# drv8313.net
KiCad netlist of a schematic drawn in Altium Designer
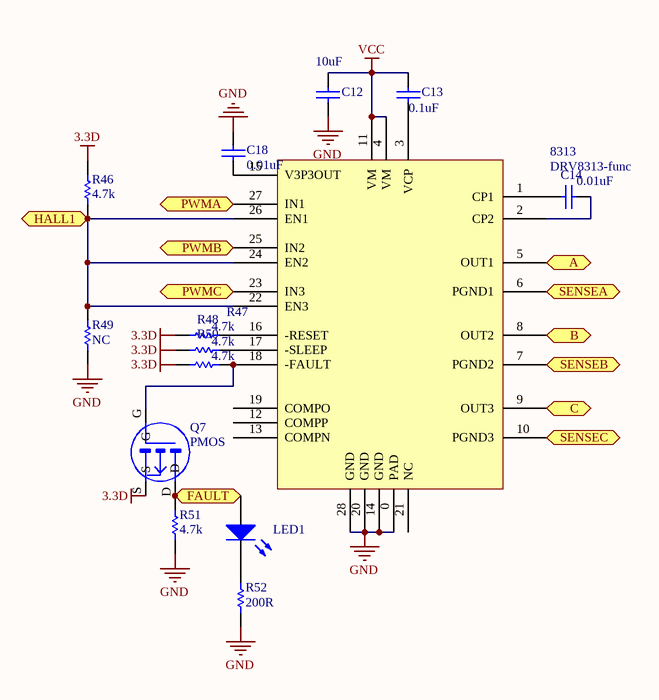
[diagram p0: drv8313.SchDoc]

(export (version "E")
  (design (tool "Eeschema 10.0.6"))
  (components
    (comp (ref "8313")
      (value "DRV8313-func")
      (footprint "DRV8313")
      (libsource (lib "sch") (part "DRV8313-func"))
    )
    (comp (ref "C12")
      (value "10uF")
      (footprint "0805")
      (description "Capacitor")
      (fields (field (name "PUBLISHER") "Altium Limited"))
      (libsource (lib "PCB_Project") (part "Cap"))
    )
    (comp (ref "C13")
      (value "0.1uF")
      (footprint "0603")
      (description "Capacitor")
      (fields (field (name "PUBLISHER") "Altium Limited"))
      (libsource (lib "PCB_Project") (part "Cap"))
    )
    (comp (ref "C14")
      (value "0.01uF")
      (footprint "0603")
      (description "Capacitor")
      (fields (field (name "PUBLISHER") "Altium Limited"))
      (libsource (lib "PCB_Project") (part "Cap"))
    )
    (comp (ref "C18")
      (value "0.01uF")
      (footprint "0603")
      (description "Capacitor")
      (fields (field (name "PUBLISHER") "Altium Limited"))
      (libsource (lib "PCB_Project") (part "Cap"))
    )
    (comp (ref "LED1")
      (value "LED0")
      (footprint "0603")
      (description "LED")
      (fields (field (name "PUBLISHER") "Altium Limited"))
      (libsource (lib "mcu_board") (part "LED0"))
    )
    (comp (ref "Q7") (value "PMOS") (footprint "SOT-23B_L") (libsource (lib "sch") (part "PMOS")))
    (comp (ref "R46")
      (value "4.7k")
      (footprint "0603")
      (description "Resistor")
      (fields (field (name "PUBLISHER") "Altium Limited"))
      (libsource (lib "Miscellaneous Devices") (part "Res1"))
    )
    (comp (ref "R47")
      (value "4.7k")
      (footprint "0603")
      (description "Resistor")
      (fields (field (name "PUBLISHER") "Altium Limited"))
      (libsource (lib "Miscellaneous Devices") (part "Res1"))
    )
    (comp (ref "R48")
      (value "4.7k")
      (footprint "0603")
      (description "Resistor")
      (fields (field (name "PUBLISHER") "Altium Limited"))
      (libsource (lib "Miscellaneous Devices") (part "Res1"))
    )
    (comp (ref "R49")
      (value "NC")
      (footprint "0603")
      (description "Resistor")
      (fields (field (name "PUBLISHER") "Altium Limited"))
      (libsource (lib "Miscellaneous Devices") (part "Res1"))
    )
    (comp (ref "R50")
      (value "4.7k")
      (footprint "0603")
      (description "Resistor")
      (fields (field (name "PUBLISHER") "Altium Limited"))
      (libsource (lib "Miscellaneous Devices") (part "Res1"))
    )
    (comp (ref "R51")
      (value "4.7k")
      (footprint "0603")
      (description "Resistor")
      (fields (field (name "PUBLISHER") "Altium Limited"))
      (libsource (lib "Miscellaneous Devices") (part "Res1"))
    )
    (comp (ref "R52")
      (value "200R")
      (footprint "0603")
      (description "Resistor")
      (fields (field (name "PUBLISHER") "Altium Limited"))
      (libsource (lib "Miscellaneous Devices") (part "Res1"))
    )
  )
  (nets
    (net (code "1") (name "/A") (class "Default")
      (node (ref "8313") (pin "5") (pinfunction "OUT1_5") (pintype "passive"))
    )
    (net (code "2") (name "/B") (class "Default")
      (node (ref "8313") (pin "8") (pinfunction "OUT2_8") (pintype "passive"))
    )
    (net (code "3") (name "/C") (class "Default")
      (node (ref "8313") (pin "9") (pinfunction "OUT3_9") (pintype "passive"))
    )
    (net (code "4") (name "/FAULT") (class "Default")
      (node (ref "LED1") (pin "1") (pinfunction "A_1") (pintype "passive"))
      (node (ref "Q7") (pin "D") (pinfunction "D_D") (pintype "passive"))
      (node (ref "R51") (pin "2") (pinfunction "2_2") (pintype "passive"))
    )
    (net (code "5") (name "/HALL1") (class "Default")
      (node (ref "8313") (pin "22") (pinfunction "EN3_22") (pintype "passive"))
      (node (ref "8313") (pin "24") (pinfunction "EN2_24") (pintype "passive"))
      (node (ref "8313") (pin "26") (pinfunction "EN1_26") (pintype "passive"))
      (node (ref "R46") (pin "2") (pinfunction "2_2") (pintype "passive"))
      (node (ref "R49") (pin "1") (pinfunction "1_1") (pintype "passive"))
    )
    (net (code "6") (name "/PWMA") (class "Default")
      (node (ref "8313") (pin "27") (pinfunction "IN1_27") (pintype "passive"))
    )
    (net (code "7") (name "/PWMB") (class "Default")
      (node (ref "8313") (pin "25") (pinfunction "IN2_25") (pintype "passive"))
    )
    (net (code "8") (name "/PWMC") (class "Default")
      (node (ref "8313") (pin "23") (pinfunction "IN3_23") (pintype "passive"))
    )
    (net (code "9") (name "/SENSEA") (class "Default")
      (node (ref "8313") (pin "6") (pinfunction "PGND1_6") (pintype "passive"))
    )
    (net (code "10") (name "/SENSEB") (class "Default")
      (node (ref "8313") (pin "7") (pinfunction "PGND2_7") (pintype "passive"))
    )
    (net (code "11") (name "/SENSEC") (class "Default")
      (node (ref "8313") (pin "10") (pinfunction "PGND3_10") (pintype "passive"))
    )
    (net (code "12") (name "3.3D") (class "Default")
      (node (ref "Q7") (pin "S") (pinfunction "S_S") (pintype "passive"))
      (node (ref "R46") (pin "1") (pinfunction "1_1") (pintype "passive"))
      (node (ref "R47") (pin "1") (pinfunction "1_1") (pintype "passive"))
      (node (ref "R48") (pin "1") (pinfunction "1_1") (pintype "passive"))
      (node (ref "R50") (pin "1") (pinfunction "1_1") (pintype "passive"))
    )
    (net (code "13") (name "GND") (class "Default")
      (node (ref "8313") (pin "0") (pinfunction "PAD_0") (pintype "passive"))
      (node (ref "8313") (pin "14") (pinfunction "GND_14") (pintype "passive"))
      (node (ref "8313") (pin "20") (pinfunction "GND_20") (pintype "passive"))
      (node (ref "8313") (pin "28") (pinfunction "GND_28") (pintype "passive"))
      (node (ref "C12") (pin "1") (pinfunction "1_1") (pintype "passive"))
      (node (ref "C18") (pin "2") (pinfunction "2_2") (pintype "passive"))
      (node (ref "R49") (pin "2") (pinfunction "2_2") (pintype "passive"))
      (node (ref "R51") (pin "1") (pinfunction "1_1") (pintype "passive"))
      (node (ref "R52") (pin "1") (pinfunction "1_1") (pintype "passive"))
    )
    (net (code "14") (name "Net-(8313--FAULT)") (class "Default")
      (node (ref "8313") (pin "18") (pinfunction "-FAULT_18") (pintype "passive"))
      (node (ref "Q7") (pin "G") (pinfunction "G_G") (pintype "passive"))
      (node (ref "R50") (pin "2") (pinfunction "2_2") (pintype "passive"))
    )
    (net (code "15") (name "Net-(8313--RESET)") (class "Default")
      (node (ref "8313") (pin "16") (pinfunction "-RESET_16") (pintype "passive"))
      (node (ref "R47") (pin "2") (pinfunction "2_2") (pintype "passive"))
    )
    (net (code "16") (name "Net-(8313--SLEEP)") (class "Default")
      (node (ref "8313") (pin "17") (pinfunction "-SLEEP_17") (pintype "passive"))
      (node (ref "R48") (pin "2") (pinfunction "2_2") (pintype "passive"))
    )
    (net (code "17") (name "Net-(8313-CP1)") (class "Default")
      (node (ref "8313") (pin "1") (pinfunction "CP1_1") (pintype "passive"))
      (node (ref "C14") (pin "1") (pinfunction "1_1") (pintype "passive"))
    )
    (net (code "18") (name "Net-(8313-CP2)") (class "Default")
      (node (ref "8313") (pin "2") (pinfunction "CP2_2") (pintype "passive"))
      (node (ref "C14") (pin "2") (pinfunction "2_2") (pintype "passive"))
    )
    (net (code "19") (name "Net-(8313-V3P3OUT)") (class "Default")
      (node (ref "8313") (pin "15") (pinfunction "V3P3OUT_15") (pintype "passive"))
      (node (ref "C18") (pin "1") (pinfunction "1_1") (pintype "passive"))
    )
    (net (code "20") (name "Net-(8313-VCP)") (class "Default")
      (node (ref "8313") (pin "3") (pinfunction "VCP_3") (pintype "passive"))
      (node (ref "C13") (pin "2") (pinfunction "2_2") (pintype "passive"))
    )
    (net (code "21") (name "Net-(LED1-K)") (class "Default")
      (node (ref "LED1") (pin "2") (pinfunction "K_2") (pintype "passive"))
      (node (ref "R52") (pin "2") (pinfunction "2_2") (pintype "passive"))
    )
    (net (code "22") (name "VCC") (class "Default")
      (node (ref "8313") (pin "11") (pinfunction "VM_11") (pintype "passive"))
      (node (ref "8313") (pin "4") (pinfunction "VM_4") (pintype "passive"))
      (node (ref "C12") (pin "2") (pinfunction "2_2") (pintype "passive"))
      (node (ref "C13") (pin "1") (pinfunction "1_1") (pintype "passive"))
    )
    (net (code "23") (name "unconnected-(8313-COMPN-Pad13)") (class "Default")
      (node (ref "8313") (pin "13") (pinfunction "COMPN_13") (pintype "passive"))
    )
    (net (code "24") (name "unconnected-(8313-COMPO-Pad19)") (class "Default")
      (node (ref "8313") (pin "19") (pinfunction "COMPO_19") (pintype "passive"))
    )
    (net (code "25") (name "unconnected-(8313-COMPP-Pad12)") (class "Default")
      (node (ref "8313") (pin "12") (pinfunction "COMPP_12") (pintype "passive"))
    )
    (net (code "26") (name "unconnected-(8313-NC-Pad21)") (class "Default")
      (node (ref "8313") (pin "21") (pinfunction "NC_21") (pintype "passive"))
    )
  )
)
